# 03_AIR724.net
KiCad netlist of a schematic drawn in Altium Designer
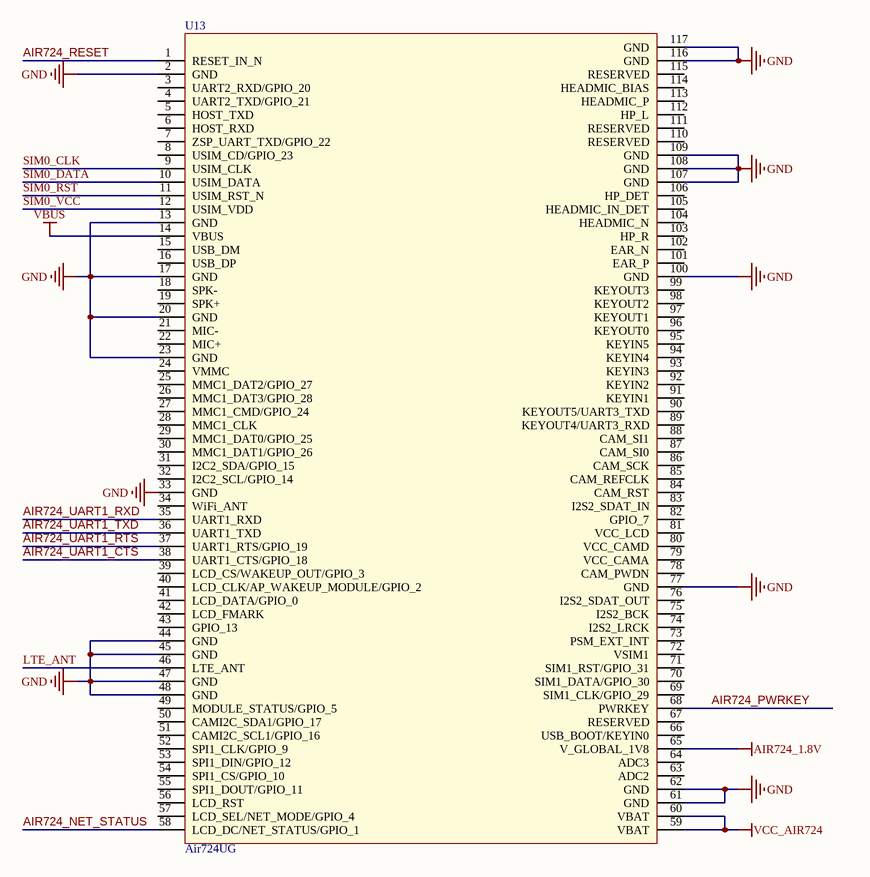
[diagram p0: 03_AIR724.SchDoc]

(export (version "E")
  (design (tool "Eeschema 10.0.6"))
  (components
    (comp (ref "U13")
      (value "Air724UG")
      (footprint "AIR724UG")
      (fields (field (name "MANUFACTURER") "Luat(合宙)") (field (name "MANUFACTURER PART") "Air724UG-NA"))
      (libsource (lib "封装库") (part "Air724UG"))
    )
  )
  (nets
    (net (code "1") (name "/AIR724_NET_STATUS") (class "Default")
      (node (ref "U13") (pin "58") (pinfunction "LCD_DC/NET_STATUS/GPIO_1_58") (pintype "passive"))
    )
    (net (code "2") (name "/AIR724_PWRKEY") (class "Default")
      (node (ref "U13") (pin "68") (pinfunction "PWRKEY_68") (pintype "passive"))
    )
    (net (code "3") (name "/AIR724_RESET") (class "Default")
      (node (ref "U13") (pin "1") (pinfunction "RESET_IN_N_1") (pintype "passive"))
    )
    (net (code "4") (name "/AIR724_UART1_CTS") (class "Default")
      (node (ref "U13") (pin "38") (pinfunction "UART1_CTS/GPIO_18_38") (pintype "passive"))
    )
    (net (code "5") (name "/AIR724_UART1_RTS") (class "Default")
      (node (ref "U13") (pin "37") (pinfunction "UART1_RTS/GPIO_19_37") (pintype "passive"))
    )
    (net (code "6") (name "/AIR724_UART1_RXD") (class "Default")
      (node (ref "U13") (pin "35") (pinfunction "UART1_RXD_35") (pintype "passive"))
    )
    (net (code "7") (name "/AIR724_UART1_TXD") (class "Default")
      (node (ref "U13") (pin "36") (pinfunction "UART1_TXD_36") (pintype "passive"))
    )
    (net (code "8") (name "/LTE_ANT") (class "Default")
      (node (ref "U13") (pin "46") (pinfunction "LTE_ANT_46") (pintype "passive"))
    )
    (net (code "9") (name "/SIM0_CLK") (class "Default")
      (node (ref "U13") (pin "9") (pinfunction "USIM_CLK_9") (pintype "passive"))
    )
    (net (code "10") (name "/SIM0_DATA") (class "Default")
      (node (ref "U13") (pin "10") (pinfunction "USIM_DATA_10") (pintype "passive"))
    )
    (net (code "11") (name "/SIM0_RST") (class "Default")
      (node (ref "U13") (pin "11") (pinfunction "USIM_RST_N_11") (pintype "passive"))
    )
    (net (code "12") (name "/SIM0_VCC") (class "Default")
      (node (ref "U13") (pin "12") (pinfunction "USIM_VDD_12") (pintype "passive"))
    )
    (net (code "13") (name "AIR724_1.8V") (class "Default")
      (node (ref "U13") (pin "65") (pinfunction "V_GLOBAL_1V8_65") (pintype "passive"))
    )
    (net (code "14") (name "GND") (class "Default")
      (node (ref "U13") (pin "100") (pinfunction "GND_100") (pintype "passive"))
      (node (ref "U13") (pin "107") (pinfunction "GND_107") (pintype "passive"))
      (node (ref "U13") (pin "108") (pinfunction "GND_108") (pintype "passive"))
      (node (ref "U13") (pin "109") (pinfunction "GND_109") (pintype "passive"))
      (node (ref "U13") (pin "116") (pinfunction "GND_116") (pintype "passive"))
      (node (ref "U13") (pin "117") (pinfunction "GND_117") (pintype "passive"))
      (node (ref "U13") (pin "13") (pinfunction "GND_13") (pintype "passive"))
      (node (ref "U13") (pin "17") (pinfunction "GND_17") (pintype "passive"))
      (node (ref "U13") (pin "2") (pinfunction "GND_2") (pintype "passive"))
      (node (ref "U13") (pin "20") (pinfunction "GND_20") (pintype "passive"))
      (node (ref "U13") (pin "23") (pinfunction "GND_23") (pintype "passive"))
      (node (ref "U13") (pin "33") (pinfunction "GND_33") (pintype "passive"))
      (node (ref "U13") (pin "44") (pinfunction "GND_44") (pintype "passive"))
      (node (ref "U13") (pin "45") (pinfunction "GND_45") (pintype "passive"))
      (node (ref "U13") (pin "47") (pinfunction "GND_47") (pintype "passive"))
      (node (ref "U13") (pin "48") (pinfunction "GND_48") (pintype "passive"))
      (node (ref "U13") (pin "61") (pinfunction "GND_61") (pintype "passive"))
      (node (ref "U13") (pin "62") (pinfunction "GND_62") (pintype "passive"))
      (node (ref "U13") (pin "77") (pinfunction "GND_77") (pintype "passive"))
    )
    (net (code "15") (name "VBUS") (class "Default")
      (node (ref "U13") (pin "14") (pinfunction "VBUS_14") (pintype "passive"))
    )
    (net (code "16") (name "VCC_AIR724") (class "Default")
      (node (ref "U13") (pin "59") (pinfunction "VBAT_59") (pintype "passive"))
      (node (ref "U13") (pin "60") (pinfunction "VBAT_60") (pintype "passive"))
    )
    (net (code "17") (name "unconnected-(U13-ADC2-Pad63)") (class "Default")
      (node (ref "U13") (pin "63") (pinfunction "ADC2_63") (pintype "passive"))
    )
    (net (code "18") (name "unconnected-(U13-ADC3-Pad64)") (class "Default")
      (node (ref "U13") (pin "64") (pinfunction "ADC3_64") (pintype "passive"))
    )
    (net (code "19") (name "unconnected-(U13-CAMI2C_SCL1{slash}GPIO_16-Pad51)") (class "Default")
      (node (ref "U13") (pin "51") (pinfunction "CAMI2C_SCL1/GPIO_16_51") (pintype "passive"))
    )
    (net (code "20") (name "unconnected-(U13-CAMI2C_SDA1{slash}GPIO_17-Pad50)") (class "Default")
      (node (ref "U13") (pin "50") (pinfunction "CAMI2C_SDA1/GPIO_17_50") (pintype "passive"))
    )
    (net (code "21") (name "unconnected-(U13-CAM_PWDN-Pad78)") (class "Default")
      (node (ref "U13") (pin "78") (pinfunction "CAM_PWDN_78") (pintype "passive"))
    )
    (net (code "22") (name "unconnected-(U13-CAM_REFCLK-Pad85)") (class "Default")
      (node (ref "U13") (pin "85") (pinfunction "CAM_REFCLK_85") (pintype "passive"))
    )
    (net (code "23") (name "unconnected-(U13-CAM_RST-Pad84)") (class "Default")
      (node (ref "U13") (pin "84") (pinfunction "CAM_RST_84") (pintype "passive"))
    )
    (net (code "24") (name "unconnected-(U13-CAM_SCK-Pad86)") (class "Default")
      (node (ref "U13") (pin "86") (pinfunction "CAM_SCK_86") (pintype "passive"))
    )
    (net (code "25") (name "unconnected-(U13-CAM_SI0-Pad87)") (class "Default")
      (node (ref "U13") (pin "87") (pinfunction "CAM_SI0_87") (pintype "passive"))
    )
    (net (code "26") (name "unconnected-(U13-CAM_SI1-Pad88)") (class "Default")
      (node (ref "U13") (pin "88") (pinfunction "CAM_SI1_88") (pintype "passive"))
    )
    (net (code "27") (name "unconnected-(U13-EAR_N-Pad102)") (class "Default")
      (node (ref "U13") (pin "102") (pinfunction "EAR_N_102") (pintype "passive"))
    )
    (net (code "28") (name "unconnected-(U13-EAR_P-Pad101)") (class "Default")
      (node (ref "U13") (pin "101") (pinfunction "EAR_P_101") (pintype "passive"))
    )
    (net (code "29") (name "unconnected-(U13-GPIO_7-Pad82)") (class "Default")
      (node (ref "U13") (pin "82") (pinfunction "GPIO_7_82") (pintype "passive"))
    )
    (net (code "30") (name "unconnected-(U13-GPIO_13-Pad43)") (class "Default")
      (node (ref "U13") (pin "43") (pinfunction "GPIO_13_43") (pintype "passive"))
    )
    (net (code "31") (name "unconnected-(U13-HEADMIC_BIAS-Pad114)") (class "Default")
      (node (ref "U13") (pin "114") (pinfunction "HEADMIC_BIAS_114") (pintype "passive"))
    )
    (net (code "32") (name "unconnected-(U13-HEADMIC_IN_DET-Pad105)") (class "Default")
      (node (ref "U13") (pin "105") (pinfunction "HEADMIC_IN_DET_105") (pintype "passive"))
    )
    (net (code "33") (name "unconnected-(U13-HEADMIC_N-Pad104)") (class "Default")
      (node (ref "U13") (pin "104") (pinfunction "HEADMIC_N_104") (pintype "passive"))
    )
    (net (code "34") (name "unconnected-(U13-HEADMIC_P-Pad113)") (class "Default")
      (node (ref "U13") (pin "113") (pinfunction "HEADMIC_P_113") (pintype "passive"))
    )
    (net (code "35") (name "unconnected-(U13-HOST_RXD-Pad6)") (class "Default")
      (node (ref "U13") (pin "6") (pinfunction "HOST_RXD_6") (pintype "passive"))
    )
    (net (code "36") (name "unconnected-(U13-HOST_TXD-Pad5)") (class "Default")
      (node (ref "U13") (pin "5") (pinfunction "HOST_TXD_5") (pintype "passive"))
    )
    (net (code "37") (name "unconnected-(U13-HP_DET-Pad106)") (class "Default")
      (node (ref "U13") (pin "106") (pinfunction "HP_DET_106") (pintype "passive"))
    )
    (net (code "38") (name "unconnected-(U13-HP_L-Pad112)") (class "Default")
      (node (ref "U13") (pin "112") (pinfunction "HP_L_112") (pintype "passive"))
    )
    (net (code "39") (name "unconnected-(U13-HP_R-Pad103)") (class "Default")
      (node (ref "U13") (pin "103") (pinfunction "HP_R_103") (pintype "passive"))
    )
    (net (code "40") (name "unconnected-(U13-I2C2_SCL{slash}GPIO_14-Pad32)") (class "Default")
      (node (ref "U13") (pin "32") (pinfunction "I2C2_SCL/GPIO_14_32") (pintype "passive"))
    )
    (net (code "41") (name "unconnected-(U13-I2C2_SDA{slash}GPIO_15-Pad31)") (class "Default")
      (node (ref "U13") (pin "31") (pinfunction "I2C2_SDA/GPIO_15_31") (pintype "passive"))
    )
    (net (code "42") (name "unconnected-(U13-I2S2_BCK-Pad75)") (class "Default")
      (node (ref "U13") (pin "75") (pinfunction "I2S2_BCK_75") (pintype "passive"))
    )
    (net (code "43") (name "unconnected-(U13-I2S2_LRCK-Pad74)") (class "Default")
      (node (ref "U13") (pin "74") (pinfunction "I2S2_LRCK_74") (pintype "passive"))
    )
    (net (code "44") (name "unconnected-(U13-I2S2_SDAT_IN-Pad83)") (class "Default")
      (node (ref "U13") (pin "83") (pinfunction "I2S2_SDAT_IN_83") (pintype "passive"))
    )
    (net (code "45") (name "unconnected-(U13-I2S2_SDAT_OUT-Pad76)") (class "Default")
      (node (ref "U13") (pin "76") (pinfunction "I2S2_SDAT_OUT_76") (pintype "passive"))
    )
    (net (code "46") (name "unconnected-(U13-KEYIN1-Pad91)") (class "Default")
      (node (ref "U13") (pin "91") (pinfunction "KEYIN1_91") (pintype "passive"))
    )
    (net (code "47") (name "unconnected-(U13-KEYIN2-Pad92)") (class "Default")
      (node (ref "U13") (pin "92") (pinfunction "KEYIN2_92") (pintype "passive"))
    )
    (net (code "48") (name "unconnected-(U13-KEYIN3-Pad93)") (class "Default")
      (node (ref "U13") (pin "93") (pinfunction "KEYIN3_93") (pintype "passive"))
    )
    (net (code "49") (name "unconnected-(U13-KEYIN4-Pad94)") (class "Default")
      (node (ref "U13") (pin "94") (pinfunction "KEYIN4_94") (pintype "passive"))
    )
    (net (code "50") (name "unconnected-(U13-KEYIN5-Pad95)") (class "Default")
      (node (ref "U13") (pin "95") (pinfunction "KEYIN5_95") (pintype "passive"))
    )
    (net (code "51") (name "unconnected-(U13-KEYOUT0-Pad96)") (class "Default")
      (node (ref "U13") (pin "96") (pinfunction "KEYOUT0_96") (pintype "passive"))
    )
    (net (code "52") (name "unconnected-(U13-KEYOUT1-Pad97)") (class "Default")
      (node (ref "U13") (pin "97") (pinfunction "KEYOUT1_97") (pintype "passive"))
    )
    (net (code "53") (name "unconnected-(U13-KEYOUT2-Pad98)") (class "Default")
      (node (ref "U13") (pin "98") (pinfunction "KEYOUT2_98") (pintype "passive"))
    )
    (net (code "54") (name "unconnected-(U13-KEYOUT3-Pad99)") (class "Default")
      (node (ref "U13") (pin "99") (pinfunction "KEYOUT3_99") (pintype "passive"))
    )
    (net (code "55") (name "unconnected-(U13-KEYOUT4{slash}UART3_RXD-Pad89)") (class "Default")
      (node (ref "U13") (pin "89") (pinfunction "KEYOUT4/UART3_RXD_89") (pintype "passive"))
    )
    (net (code "56") (name "unconnected-(U13-KEYOUT5{slash}UART3_TXD-Pad90)") (class "Default")
      (node (ref "U13") (pin "90") (pinfunction "KEYOUT5/UART3_TXD_90") (pintype "passive"))
    )
    (net (code "57") (name "unconnected-(U13-LCD_CLK{slash}AP_WAKEUP_MODULE{slash}GPIO_2-Pad40)") (class "Default")
      (node (ref "U13") (pin "40") (pinfunction "LCD_CLK/AP_WAKEUP_MODULE/GPIO_2_40") (pintype "passive"))
    )
    (net (code "58") (name "unconnected-(U13-LCD_CS{slash}WAKEUP_OUT{slash}GPIO_3-Pad39)") (class "Default")
      (node (ref "U13") (pin "39") (pinfunction "LCD_CS/WAKEUP_OUT/GPIO_3_39") (pintype "passive"))
    )
    (net (code "59") (name "unconnected-(U13-LCD_DATA{slash}GPIO_0-Pad41)") (class "Default")
      (node (ref "U13") (pin "41") (pinfunction "LCD_DATA/GPIO_0_41") (pintype "passive"))
    )
    (net (code "60") (name "unconnected-(U13-LCD_FMARK-Pad42)") (class "Default")
      (node (ref "U13") (pin "42") (pinfunction "LCD_FMARK_42") (pintype "passive"))
    )
    (net (code "61") (name "unconnected-(U13-LCD_RST-Pad56)") (class "Default")
      (node (ref "U13") (pin "56") (pinfunction "LCD_RST_56") (pintype "passive"))
    )
    (net (code "62") (name "unconnected-(U13-LCD_SEL{slash}NET_MODE{slash}GPIO_4-Pad57)") (class "Default")
      (node (ref "U13") (pin "57") (pinfunction "LCD_SEL/NET_MODE/GPIO_4_57") (pintype "passive"))
    )
    (net (code "63") (name "unconnected-(U13-MIC+-Pad22)") (class "Default")
      (node (ref "U13") (pin "22") (pinfunction "MIC+_22") (pintype "passive"))
    )
    (net (code "64") (name "unconnected-(U13-MIC--Pad21)") (class "Default")
      (node (ref "U13") (pin "21") (pinfunction "MIC-_21") (pintype "passive"))
    )
    (net (code "65") (name "unconnected-(U13-MMC1_CLK-Pad28)") (class "Default")
      (node (ref "U13") (pin "28") (pinfunction "MMC1_CLK_28") (pintype "passive"))
    )
    (net (code "66") (name "unconnected-(U13-MMC1_CMD{slash}GPIO_24-Pad27)") (class "Default")
      (node (ref "U13") (pin "27") (pinfunction "MMC1_CMD/GPIO_24_27") (pintype "passive"))
    )
    (net (code "67") (name "unconnected-(U13-MMC1_DAT0{slash}GPIO_25-Pad29)") (class "Default")
      (node (ref "U13") (pin "29") (pinfunction "MMC1_DAT0/GPIO_25_29") (pintype "passive"))
    )
    (net (code "68") (name "unconnected-(U13-MMC1_DAT1{slash}GPIO_26-Pad30)") (class "Default")
      (node (ref "U13") (pin "30") (pinfunction "MMC1_DAT1/GPIO_26_30") (pintype "passive"))
    )
    (net (code "69") (name "unconnected-(U13-MMC1_DAT2{slash}GPIO_27-Pad25)") (class "Default")
      (node (ref "U13") (pin "25") (pinfunction "MMC1_DAT2/GPIO_27_25") (pintype "passive"))
    )
    (net (code "70") (name "unconnected-(U13-MMC1_DAT3{slash}GPIO_28-Pad26)") (class "Default")
      (node (ref "U13") (pin "26") (pinfunction "MMC1_DAT3/GPIO_28_26") (pintype "passive"))
    )
    (net (code "71") (name "unconnected-(U13-MODULE_STATUS{slash}GPIO_5-Pad49)") (class "Default")
      (node (ref "U13") (pin "49") (pinfunction "MODULE_STATUS/GPIO_5_49") (pintype "passive"))
    )
    (net (code "72") (name "unconnected-(U13-PSM_EXT_INT-Pad73)") (class "Default")
      (node (ref "U13") (pin "73") (pinfunction "PSM_EXT_INT_73") (pintype "passive"))
    )
    (net (code "73") (name "unconnected-(U13-RESERVED-Pad67)") (class "Default")
      (node (ref "U13") (pin "67") (pinfunction "RESERVED_67") (pintype "passive"))
    )
    (net (code "74") (name "unconnected-(U13-RESERVED-Pad110)") (class "Default")
      (node (ref "U13") (pin "110") (pinfunction "RESERVED_110") (pintype "passive"))
    )
    (net (code "75") (name "unconnected-(U13-RESERVED-Pad111)") (class "Default")
      (node (ref "U13") (pin "111") (pinfunction "RESERVED_111") (pintype "passive"))
    )
    (net (code "76") (name "unconnected-(U13-RESERVED-Pad115)") (class "Default")
      (node (ref "U13") (pin "115") (pinfunction "RESERVED_115") (pintype "passive"))
    )
    (net (code "77") (name "unconnected-(U13-SIM1_CLK{slash}GPIO_29-Pad69)") (class "Default")
      (node (ref "U13") (pin "69") (pinfunction "SIM1_CLK/GPIO_29_69") (pintype "passive"))
    )
    (net (code "78") (name "unconnected-(U13-SIM1_DATA{slash}GPIO_30-Pad70)") (class "Default")
      (node (ref "U13") (pin "70") (pinfunction "SIM1_DATA/GPIO_30_70") (pintype "passive"))
    )
    (net (code "79") (name "unconnected-(U13-SIM1_RST{slash}GPIO_31-Pad71)") (class "Default")
      (node (ref "U13") (pin "71") (pinfunction "SIM1_RST/GPIO_31_71") (pintype "passive"))
    )
    (net (code "80") (name "unconnected-(U13-SPI1_CLK{slash}GPIO_9-Pad52)") (class "Default")
      (node (ref "U13") (pin "52") (pinfunction "SPI1_CLK/GPIO_9_52") (pintype "passive"))
    )
    (net (code "81") (name "unconnected-(U13-SPI1_CS{slash}GPIO_10-Pad54)") (class "Default")
      (node (ref "U13") (pin "54") (pinfunction "SPI1_CS/GPIO_10_54") (pintype "passive"))
    )
    (net (code "82") (name "unconnected-(U13-SPI1_DIN{slash}GPIO_12-Pad53)") (class "Default")
      (node (ref "U13") (pin "53") (pinfunction "SPI1_DIN/GPIO_12_53") (pintype "passive"))
    )
    (net (code "83") (name "unconnected-(U13-SPI1_DOUT{slash}GPIO_11-Pad55)") (class "Default")
      (node (ref "U13") (pin "55") (pinfunction "SPI1_DOUT/GPIO_11_55") (pintype "passive"))
    )
    (net (code "84") (name "unconnected-(U13-SPK+-Pad19)") (class "Default")
      (node (ref "U13") (pin "19") (pinfunction "SPK+_19") (pintype "passive"))
    )
    (net (code "85") (name "unconnected-(U13-SPK--Pad18)") (class "Default")
      (node (ref "U13") (pin "18") (pinfunction "SPK-_18") (pintype "passive"))
    )
    (net (code "86") (name "unconnected-(U13-UART2_RXD{slash}GPIO_20-Pad3)") (class "Default")
      (node (ref "U13") (pin "3") (pinfunction "UART2_RXD/GPIO_20_3") (pintype "passive"))
    )
    (net (code "87") (name "unconnected-(U13-UART2_TXD{slash}GPIO_21-Pad4)") (class "Default")
      (node (ref "U13") (pin "4") (pinfunction "UART2_TXD/GPIO_21_4") (pintype "passive"))
    )
    (net (code "88") (name "unconnected-(U13-USB_BOOT{slash}KEYIN0-Pad66)") (class "Default")
      (node (ref "U13") (pin "66") (pinfunction "USB_BOOT/KEYIN0_66") (pintype "passive"))
    )
    (net (code "89") (name "unconnected-(U13-USB_DM-Pad15)") (class "Default")
      (node (ref "U13") (pin "15") (pinfunction "USB_DM_15") (pintype "passive"))
    )
    (net (code "90") (name "unconnected-(U13-USB_DP-Pad16)") (class "Default")
      (node (ref "U13") (pin "16") (pinfunction "USB_DP_16") (pintype "passive"))
    )
    (net (code "91") (name "unconnected-(U13-USIM_CD{slash}GPIO_23-Pad8)") (class "Default")
      (node (ref "U13") (pin "8") (pinfunction "USIM_CD/GPIO_23_8") (pintype "passive"))
    )
    (net (code "92") (name "unconnected-(U13-VCC_CAMA-Pad79)") (class "Default")
      (node (ref "U13") (pin "79") (pinfunction "VCC_CAMA_79") (pintype "passive"))
    )
    (net (code "93") (name "unconnected-(U13-VCC_CAMD-Pad80)") (class "Default")
      (node (ref "U13") (pin "80") (pinfunction "VCC_CAMD_80") (pintype "passive"))
    )
    (net (code "94") (name "unconnected-(U13-VCC_LCD-Pad81)") (class "Default")
      (node (ref "U13") (pin "81") (pinfunction "VCC_LCD_81") (pintype "passive"))
    )
    (net (code "95") (name "unconnected-(U13-VMMC-Pad24)") (class "Default")
      (node (ref "U13") (pin "24") (pinfunction "VMMC_24") (pintype "passive"))
    )
    (net (code "96") (name "unconnected-(U13-VSIM1-Pad72)") (class "Default")
      (node (ref "U13") (pin "72") (pinfunction "VSIM1_72") (pintype "passive"))
    )
    (net (code "97") (name "unconnected-(U13-WiFi_ANT-Pad34)") (class "Default")
      (node (ref "U13") (pin "34") (pinfunction "WiFi_ANT_34") (pintype "passive"))
    )
    (net (code "98") (name "unconnected-(U13-ZSP_UART_TXD{slash}GPIO_22-Pad7)") (class "Default")
      (node (ref "U13") (pin "7") (pinfunction "ZSP_UART_TXD/GPIO_22_7") (pintype "passive"))
    )
  )
)
